# team8_solar_tester.net
KiCad netlist of a schematic drawn in EAGLE
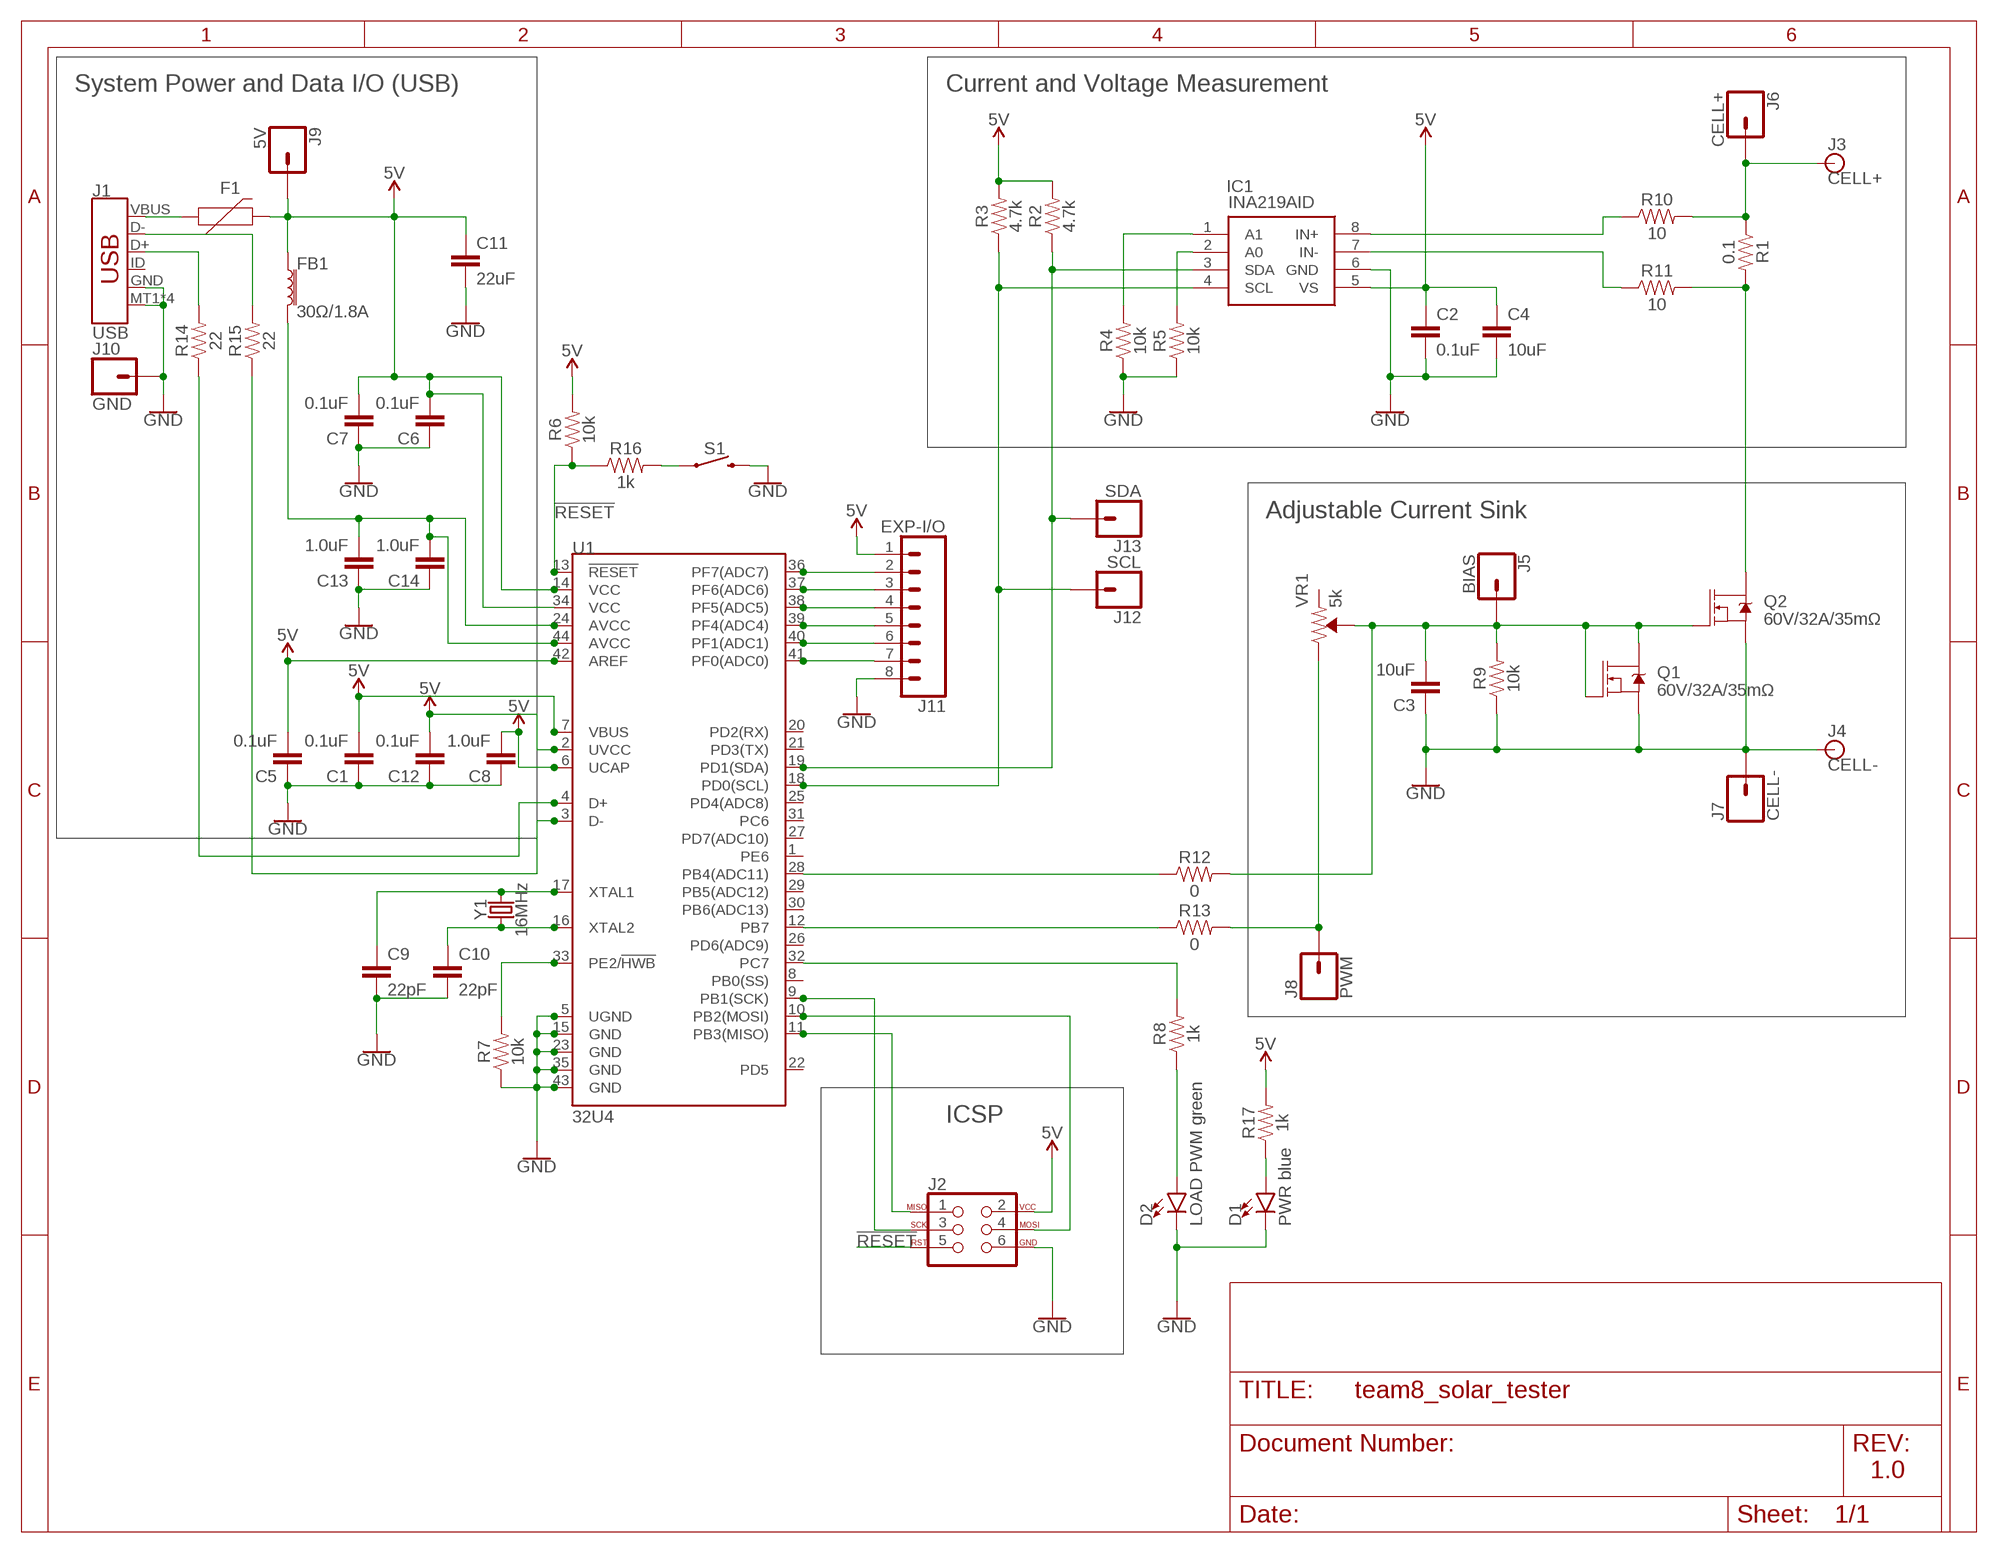
[diagram p0: schematic, sheet 1]

(export (version "E")
  (design (tool "Eeschema 10.0.6"))
  (components
    (comp (ref "C1")
      (value "0.1uF")
      (footprint "eagle-import:0603")
      (libsource (lib "eagle-import") (part "0.1UF-0603-25V-5%"))
    )
    (comp (ref "C2")
      (value "0.1uF")
      (footprint "eagle-import:0603")
      (libsource (lib "eagle-import") (part "0.1UF-0603-25V-5%"))
    )
    (comp (ref "C3")
      (value "10uF")
      (footprint "eagle-import:0805")
      (libsource (lib "eagle-import") (part "10UF-0805-10V-10%"))
    )
    (comp (ref "C4")
      (value "10uF")
      (footprint "eagle-import:0805")
      (libsource (lib "eagle-import") (part "10UF-0805-10V-10%"))
    )
    (comp (ref "C5")
      (value "0.1uF")
      (footprint "eagle-import:0603")
      (libsource (lib "eagle-import") (part "0.1UF-0603-25V-5%"))
    )
    (comp (ref "C6")
      (value "0.1uF")
      (footprint "eagle-import:0603")
      (libsource (lib "eagle-import") (part "0.1UF-0603-25V-5%"))
    )
    (comp (ref "C7")
      (value "0.1uF")
      (footprint "eagle-import:0603")
      (libsource (lib "eagle-import") (part "0.1UF-0603-25V-5%"))
    )
    (comp (ref "C8")
      (value "1.0uF")
      (footprint "eagle-import:0603")
      (libsource (lib "eagle-import") (part "1.0UF-0603-16V-10%"))
    )
    (comp (ref "C9")
      (value "22pF")
      (footprint "eagle-import:0603")
      (libsource (lib "eagle-import") (part "22PF-0603-50V-5%"))
    )
    (comp (ref "C10")
      (value "22pF")
      (footprint "eagle-import:0603")
      (libsource (lib "eagle-import") (part "22PF-0603-50V-5%"))
    )
    (comp (ref "C11")
      (value "22uF")
      (footprint "eagle-import:0805")
      (libsource (lib "eagle-import") (part "22UF-0805-6.3V-20%"))
    )
    (comp (ref "C12")
      (value "0.1uF")
      (footprint "eagle-import:0603")
      (libsource (lib "eagle-import") (part "0.1UF-0603-25V-5%"))
    )
    (comp (ref "C13")
      (value "1.0uF")
      (footprint "eagle-import:0603")
      (libsource (lib "eagle-import") (part "1.0UF-0603-16V-10%"))
    )
    (comp (ref "C14")
      (value "1.0uF")
      (footprint "eagle-import:0603")
      (libsource (lib "eagle-import") (part "1.0UF-0603-16V-10%"))
    )
    (comp (ref "D1")
      (value "PWR blue")
      (footprint "eagle-import:LED-0603")
      (libsource (lib "eagle-import") (part "LED-BLUE0603"))
    )
    (comp (ref "D2")
      (value "LOAD PWM green")
      (footprint "eagle-import:LED-0603")
      (libsource (lib "eagle-import") (part "LED-GREEN0603"))
    )
    (comp (ref "F1")
      (value "PPTC_6V500MA")
      (footprint "eagle-import:0805")
      (libsource (lib "eagle-import") (part "PPTC_6V500MA"))
    )
    (comp (ref "FB1")
      (value "30Ω/1.8A")
      (footprint "eagle-import:0603")
      (libsource (lib "eagle-import") (part "FERRITE_BEAD-0603"))
    )
    (comp (ref "IC1")
      (value "INA219AID")
      (footprint "eagle-import:SOIC127P600X175-8N")
      (fields (field (name "MOUSER_PART_NUMBER") "595-INA219AID"))
      (libsource (lib "eagle-import") (part "INA219AID"))
    )
    (comp (ref "J1")
      (value "USB")
      (footprint "eagle-import:USB-MICROB")
      (libsource (lib "eagle-import") (part "USB_MICRO-B_SMT"))
    )
    (comp (ref "J2")
      (value "AVR_SPI_PROG_3X2PTH")
      (footprint "eagle-import:2X3")
      (libsource (lib "eagle-import") (part "AVR_SPI_PROG_3X2PTH"))
    )
    (comp (ref "J3")
      (value "CELL+")
      (footprint "eagle-import:BANANA_CONN")
      (libsource (lib "eagle-import") (part "BANANA_CONN"))
    )
    (comp (ref "J4")
      (value "CELL-")
      (footprint "eagle-import:BANANA_CONN")
      (libsource (lib "eagle-import") (part "BANANA_CONN"))
    )
    (comp (ref "J5")
      (value "BIAS")
      (footprint "eagle-import:1X01")
      (libsource (lib "eagle-import") (part "CONN_01"))
    )
    (comp (ref "J6")
      (value "CELL+")
      (footprint "eagle-import:1X01")
      (libsource (lib "eagle-import") (part "CONN_01"))
    )
    (comp (ref "J7")
      (value "CELL-")
      (footprint "eagle-import:1X01")
      (libsource (lib "eagle-import") (part "CONN_01"))
    )
    (comp (ref "J8")
      (value "PWM")
      (footprint "eagle-import:1X01")
      (libsource (lib "eagle-import") (part "CONN_01"))
    )
    (comp (ref "J9")
      (value "5V")
      (footprint "eagle-import:1X01")
      (libsource (lib "eagle-import") (part "CONN_01"))
    )
    (comp (ref "J10")
      (value "GND")
      (footprint "eagle-import:1X01")
      (libsource (lib "eagle-import") (part "CONN_01"))
    )
    (comp (ref "J11")
      (value "EXP-I/O")
      (footprint "eagle-import:1X08_LONGPADS")
      (libsource (lib "eagle-import") (part "CONN_08LONGPADS"))
    )
    (comp (ref "J12")
      (value "SCL")
      (footprint "eagle-import:1X01")
      (libsource (lib "eagle-import") (part "CONN_01"))
    )
    (comp (ref "J13")
      (value "SDA")
      (footprint "eagle-import:1X01")
      (libsource (lib "eagle-import") (part "CONN_01"))
    )
    (comp (ref "Q1")
      (value "60V/32A/35mΩ")
      (footprint "eagle-import:TO220V")
      (libsource (lib "eagle-import") (part "MOSFET-NCH-FQP30N06L"))
    )
    (comp (ref "Q2")
      (value "60V/32A/35mΩ")
      (footprint "eagle-import:TO220V")
      (libsource (lib "eagle-import") (part "MOSFET-NCH-FQP30N06L"))
    )
    (comp (ref "R1")
      (value "0.1")
      (footprint "eagle-import:1210")
      (libsource (lib "eagle-import") (part "0.1OHM-1210-1/2W-1%"))
    )
    (comp (ref "R2")
      (value "4.7k")
      (footprint "eagle-import:0603")
      (libsource (lib "eagle-import") (part "4.7KOHM-0603-1/10W-1%"))
    )
    (comp (ref "R3")
      (value "4.7k")
      (footprint "eagle-import:0603")
      (libsource (lib "eagle-import") (part "4.7KOHM-0603-1/10W-1%"))
    )
    (comp (ref "R4")
      (value "10k")
      (footprint "eagle-import:0603")
      (libsource (lib "eagle-import") (part "10KOHM-0603-1/10W-1%"))
    )
    (comp (ref "R5")
      (value "10k")
      (footprint "eagle-import:0603")
      (libsource (lib "eagle-import") (part "10KOHM-0603-1/10W-1%"))
    )
    (comp (ref "R6")
      (value "10k")
      (footprint "eagle-import:0603")
      (libsource (lib "eagle-import") (part "10KOHM-0603-1/10W-1%"))
    )
    (comp (ref "R7")
      (value "10k")
      (footprint "eagle-import:0603")
      (libsource (lib "eagle-import") (part "10KOHM-0603-1/10W-1%"))
    )
    (comp (ref "R8")
      (value "1k")
      (footprint "eagle-import:0603")
      (libsource (lib "eagle-import") (part "1KOHM-0603-1/10W-1%"))
    )
    (comp (ref "R9")
      (value "10k")
      (footprint "eagle-import:0603")
      (libsource (lib "eagle-import") (part "10KOHM-0603-1/10W-1%"))
    )
    (comp (ref "R10")
      (value "10")
      (footprint "eagle-import:0603")
      (libsource (lib "eagle-import") (part "10OHM-0603-1/10W-1%"))
    )
    (comp (ref "R11")
      (value "10")
      (footprint "eagle-import:0603")
      (libsource (lib "eagle-import") (part "10OHM-0603-1/10W-1%"))
    )
    (comp (ref "R12")
      (value "0")
      (footprint "eagle-import:0603")
      (libsource (lib "eagle-import") (part "0OHM-0603-1/10W-5%"))
    )
    (comp (ref "R13")
      (value "0")
      (footprint "eagle-import:0603")
      (libsource (lib "eagle-import") (part "0OHM-0603-1/10W-5%"))
    )
    (comp (ref "R14")
      (value "22")
      (footprint "eagle-import:0603")
      (libsource (lib "eagle-import") (part "22OHM-0603-1/10W-1%"))
    )
    (comp (ref "R15")
      (value "22")
      (footprint "eagle-import:0603")
      (libsource (lib "eagle-import") (part "22OHM-0603-1/10W-1%"))
    )
    (comp (ref "R16")
      (value "1k")
      (footprint "eagle-import:0603")
      (libsource (lib "eagle-import") (part "1KOHM-0603-1/10W-1%"))
    )
    (comp (ref "R17")
      (value "1k")
      (footprint "eagle-import:0603")
      (libsource (lib "eagle-import") (part "1KOHM-0603-1/10W-1%"))
    )
    (comp (ref "S1")
      (value "MOMENTARY-SWITCH-SPST-PTH-6.0MM")
      (footprint "eagle-import:TACTILE_SWITCH_PTH_6.0MM")
      (libsource (lib "eagle-import") (part "MOMENTARY-SWITCH-SPST-PTH-6.0MM"))
    )
    (comp (ref "U1")
      (value "32U4")
      (footprint "eagle-import:QFN-44")
      (libsource (lib "eagle-import") (part "ATMEGA32U4QFN"))
    )
    (comp (ref "VR1")
      (value "5k")
      (footprint "eagle-import:TRIMPOT-SMD-5MM")
      (libsource (lib "eagle-import") (part "TRIMPOT-SMD-5MM-CLOSED-1/4W-20%"))
    )
    (comp (ref "Y1")
      (value "16MHz")
      (footprint "eagle-import:CRYSTAL-SMD-5X3.2-4PAD")
      (libsource (lib "eagle-import") (part "CRYSTAL-16MHZSMD-5X3.2"))
    )
  )
  (nets
    (net (code "1") (name "/~{RESET}") (class "Default")
      (node (ref "J2") (pin "5") (pinfunction "5_5") (pintype "passive"))
      (node (ref "R16") (pin "1") (pinfunction "1_1") (pintype "passive"))
      (node (ref "R6") (pin "1") (pinfunction "1_1") (pintype "passive"))
      (node (ref "U1") (pin "13") (pinfunction "~{RESET}_13") (pintype "bidirectional"))
    )
    (net (code "2") (name "5V") (class "Default")
      (node (ref "C1") (pin "2") (pinfunction "2_2") (pintype "passive"))
      (node (ref "C11") (pin "1") (pinfunction "1_1") (pintype "passive"))
      (node (ref "C12") (pin "2") (pinfunction "2_2") (pintype "passive"))
      (node (ref "C2") (pin "1") (pinfunction "1_1") (pintype "passive"))
      (node (ref "C4") (pin "1") (pinfunction "1_1") (pintype "passive"))
      (node (ref "C5") (pin "2") (pinfunction "2_2") (pintype "passive"))
      (node (ref "C6") (pin "2") (pinfunction "2_2") (pintype "passive"))
      (node (ref "C7") (pin "2") (pinfunction "2_2") (pintype "passive"))
      (node (ref "C8") (pin "2") (pinfunction "2_2") (pintype "passive"))
      (node (ref "F1") (pin "2") (pinfunction "2_2") (pintype "bidirectional"))
      (node (ref "FB1") (pin "1") (pinfunction "1_1") (pintype "passive"))
      (node (ref "IC1") (pin "5") (pinfunction "VS_5") (pintype "bidirectional"))
      (node (ref "J11") (pin "1") (pinfunction "1_1") (pintype "passive"))
      (node (ref "J2") (pin "2") (pinfunction "2_2") (pintype "passive"))
      (node (ref "J9") (pin "1") (pinfunction "1_1") (pintype "passive"))
      (node (ref "R17") (pin "2") (pinfunction "2_2") (pintype "passive"))
      (node (ref "R2") (pin "2") (pinfunction "2_2") (pintype "passive"))
      (node (ref "R3") (pin "2") (pinfunction "2_2") (pintype "passive"))
      (node (ref "R6") (pin "2") (pinfunction "2_2") (pintype "passive"))
      (node (ref "U1") (pin "14") (pinfunction "VCC_14") (pintype "bidirectional"))
      (node (ref "U1") (pin "2") (pinfunction "UVCC_2") (pintype "bidirectional"))
      (node (ref "U1") (pin "34") (pinfunction "VCC_34") (pintype "bidirectional"))
      (node (ref "U1") (pin "42") (pinfunction "AREF_42") (pintype "bidirectional"))
      (node (ref "U1") (pin "6") (pinfunction "UCAP_6") (pintype "bidirectional"))
      (node (ref "U1") (pin "7") (pinfunction "VBUS_7") (pintype "bidirectional"))
    )
    (net (code "3") (name "GND") (class "Default")
      (node (ref "C1") (pin "1") (pinfunction "1_1") (pintype "passive"))
      (node (ref "C10") (pin "2") (pinfunction "2_2") (pintype "passive"))
      (node (ref "C11") (pin "2") (pinfunction "2_2") (pintype "passive"))
      (node (ref "C12") (pin "1") (pinfunction "1_1") (pintype "passive"))
      (node (ref "C13") (pin "1") (pinfunction "1_1") (pintype "passive"))
      (node (ref "C14") (pin "1") (pinfunction "1_1") (pintype "passive"))
      (node (ref "C2") (pin "2") (pinfunction "2_2") (pintype "passive"))
      (node (ref "C3") (pin "1") (pinfunction "1_1") (pintype "passive"))
      (node (ref "C4") (pin "2") (pinfunction "2_2") (pintype "passive"))
      (node (ref "C5") (pin "1") (pinfunction "1_1") (pintype "passive"))
      (node (ref "C6") (pin "1") (pinfunction "1_1") (pintype "passive"))
      (node (ref "C7") (pin "1") (pinfunction "1_1") (pintype "passive"))
      (node (ref "C8") (pin "1") (pinfunction "1_1") (pintype "passive"))
      (node (ref "C9") (pin "2") (pinfunction "2_2") (pintype "passive"))
      (node (ref "D1") (pin "C") (pinfunction "C_C") (pintype "passive"))
      (node (ref "D2") (pin "C") (pinfunction "C_C") (pintype "passive"))
      (node (ref "IC1") (pin "6") (pinfunction "GND_6") (pintype "bidirectional"))
      (node (ref "J1") (pin "GND") (pinfunction "GND_GND") (pintype "power_in"))
      (node (ref "J1") (pin "MT1") (pinfunction "SHIELD_MT1") (pintype "bidirectional"))
      (node (ref "J1") (pin "MT2") (pinfunction "SHIELD_MT2") (pintype "bidirectional"))
      (node (ref "J1") (pin "P$1") (pinfunction "SHIELD_P$1") (pintype "bidirectional"))
      (node (ref "J1") (pin "P$2") (pinfunction "SHIELD_P$2") (pintype "bidirectional"))
      (node (ref "J10") (pin "1") (pinfunction "1_1") (pintype "passive"))
      (node (ref "J11") (pin "8") (pinfunction "8_8") (pintype "passive"))
      (node (ref "J2") (pin "6") (pinfunction "6_6") (pintype "passive"))
      (node (ref "J4") (pin "P$1") (pinfunction "1_P$1") (pintype "passive"))
      (node (ref "J7") (pin "1") (pinfunction "1_1") (pintype "passive"))
      (node (ref "Q1") (pin "3") (pinfunction "S_3") (pintype "bidirectional"))
      (node (ref "Q2") (pin "3") (pinfunction "S_3") (pintype "bidirectional"))
      (node (ref "R4") (pin "1") (pinfunction "1_1") (pintype "passive"))
      (node (ref "R5") (pin "1") (pinfunction "1_1") (pintype "passive"))
      (node (ref "R7") (pin "1") (pinfunction "1_1") (pintype "passive"))
      (node (ref "R9") (pin "1") (pinfunction "1_1") (pintype "passive"))
      (node (ref "S1") (pin "3") (pinfunction "2_3") (pintype "passive"))
      (node (ref "U1") (pin "15") (pinfunction "GND_15") (pintype "bidirectional"))
      (node (ref "U1") (pin "23") (pinfunction "GND_23") (pintype "bidirectional"))
      (node (ref "U1") (pin "35") (pinfunction "GND_35") (pintype "bidirectional"))
      (node (ref "U1") (pin "43") (pinfunction "GND_43") (pintype "bidirectional"))
      (node (ref "U1") (pin "5") (pinfunction "UGND_5") (pintype "bidirectional"))
    )
    (net (code "4") (name "Net-(C13-Pad2)") (class "Default")
      (node (ref "C13") (pin "2") (pinfunction "2_2") (pintype "passive"))
      (node (ref "C14") (pin "2") (pinfunction "2_2") (pintype "passive"))
      (node (ref "FB1") (pin "2") (pinfunction "2_2") (pintype "passive"))
      (node (ref "U1") (pin "24") (pinfunction "AVCC_24") (pintype "bidirectional"))
      (node (ref "U1") (pin "44") (pinfunction "AVCC_44") (pintype "bidirectional"))
    )
    (net (code "5") (name "Net-(D1-PadA)") (class "Default")
      (node (ref "D1") (pin "A") (pinfunction "A_A") (pintype "passive"))
      (node (ref "R17") (pin "1") (pinfunction "1_1") (pintype "passive"))
    )
    (net (code "6") (name "Net-(D2-PadA)") (class "Default")
      (node (ref "D2") (pin "A") (pinfunction "A_A") (pintype "passive"))
      (node (ref "R8") (pin "1") (pinfunction "1_1") (pintype "passive"))
    )
    (net (code "7") (name "Net-(F1-Pad1)") (class "Default")
      (node (ref "F1") (pin "1") (pinfunction "1_1") (pintype "bidirectional"))
      (node (ref "J1") (pin "VBUS") (pinfunction "VBUS_VBUS") (pintype "power_in"))
    )
    (net (code "8") (name "Net-(IC1-A0)") (class "Default")
      (node (ref "IC1") (pin "2") (pinfunction "A0_2") (pintype "bidirectional"))
      (node (ref "R5") (pin "2") (pinfunction "2_2") (pintype "passive"))
    )
    (net (code "9") (name "Net-(IC1-A1)") (class "Default")
      (node (ref "IC1") (pin "1") (pinfunction "A1_1") (pintype "bidirectional"))
      (node (ref "R4") (pin "2") (pinfunction "2_2") (pintype "passive"))
    )
    (net (code "10") (name "Net-(IC1-IN+)") (class "Default")
      (node (ref "IC1") (pin "8") (pinfunction "IN+_8") (pintype "bidirectional"))
      (node (ref "R10") (pin "1") (pinfunction "1_1") (pintype "passive"))
    )
    (net (code "11") (name "Net-(IC1-IN-)") (class "Default")
      (node (ref "IC1") (pin "7") (pinfunction "IN-_7") (pintype "bidirectional"))
      (node (ref "R11") (pin "1") (pinfunction "1_1") (pintype "passive"))
    )
    (net (code "12") (name "Net-(IC1-SCL)") (class "Default")
      (node (ref "IC1") (pin "4") (pinfunction "SCL_4") (pintype "bidirectional"))
      (node (ref "J12") (pin "1") (pinfunction "1_1") (pintype "passive"))
      (node (ref "R3") (pin "1") (pinfunction "1_1") (pintype "passive"))
      (node (ref "U1") (pin "18") (pinfunction "PD0(SCL)_18") (pintype "bidirectional"))
    )
    (net (code "13") (name "Net-(IC1-SDA)") (class "Default")
      (node (ref "IC1") (pin "3") (pinfunction "SDA_3") (pintype "bidirectional"))
      (node (ref "J13") (pin "1") (pinfunction "1_1") (pintype "passive"))
      (node (ref "R2") (pin "1") (pinfunction "1_1") (pintype "passive"))
      (node (ref "U1") (pin "19") (pinfunction "PD1(SDA)_19") (pintype "bidirectional"))
    )
    (net (code "14") (name "Net-(J1-PadD+)") (class "Default")
      (node (ref "J1") (pin "D+") (pinfunction "D+_D+") (pintype "bidirectional"))
      (node (ref "R14") (pin "2") (pinfunction "2_2") (pintype "passive"))
    )
    (net (code "15") (name "Net-(J1-PadD-)") (class "Default")
      (node (ref "J1") (pin "D-") (pinfunction "D-_D-") (pintype "bidirectional"))
      (node (ref "R15") (pin "2") (pinfunction "2_2") (pintype "passive"))
    )
    (net (code "16") (name "Net-(J3-1)") (class "Default")
      (node (ref "J3") (pin "P$1") (pinfunction "1_P$1") (pintype "passive"))
      (node (ref "J6") (pin "1") (pinfunction "1_1") (pintype "passive"))
      (node (ref "R1") (pin "1") (pinfunction "1_1") (pintype "passive"))
      (node (ref "R10") (pin "2") (pinfunction "2_2") (pintype "passive"))
    )
    (net (code "17") (name "Net-(Q1-D)") (class "Default")
      (node (ref "C3") (pin "2") (pinfunction "2_2") (pintype "passive"))
      (node (ref "J5") (pin "1") (pinfunction "1_1") (pintype "passive"))
      (node (ref "Q1") (pin "1") (pinfunction "G_1") (pintype "bidirectional"))
      (node (ref "Q1") (pin "2") (pinfunction "D_2") (pintype "bidirectional"))
      (node (ref "Q2") (pin "1") (pinfunction "G_1") (pintype "bidirectional"))
      (node (ref "R12") (pin "2") (pinfunction "2_2") (pintype "passive"))
      (node (ref "R9") (pin "2") (pinfunction "2_2") (pintype "passive"))
      (node (ref "VR1") (pin "B") (pinfunction "WIPER_B") (pintype "passive"))
    )
    (net (code "18") (name "Net-(Q2-D)") (class "Default")
      (node (ref "Q2") (pin "2") (pinfunction "D_2") (pintype "bidirectional"))
      (node (ref "R1") (pin "2") (pinfunction "2_2") (pintype "passive"))
      (node (ref "R11") (pin "2") (pinfunction "2_2") (pintype "passive"))
    )
    (net (code "19") (name "Net-(R16-Pad2)") (class "Default")
      (node (ref "R16") (pin "2") (pinfunction "2_2") (pintype "passive"))
      (node (ref "S1") (pin "1") (pinfunction "1_1") (pintype "passive"))
    )
    (net (code "20") (name "Net-(U1-D+)") (class "Default")
      (node (ref "R14") (pin "1") (pinfunction "1_1") (pintype "passive"))
      (node (ref "U1") (pin "4") (pinfunction "D+_4") (pintype "bidirectional"))
    )
    (net (code "21") (name "Net-(U1-D-)") (class "Default")
      (node (ref "R15") (pin "1") (pinfunction "1_1") (pintype "passive"))
      (node (ref "U1") (pin "3") (pinfunction "D-_3") (pintype "bidirectional"))
    )
    (net (code "22") (name "Net-(U1-PB1(SCK))") (class "Default")
      (node (ref "J2") (pin "3") (pinfunction "3_3") (pintype "passive"))
      (node (ref "U1") (pin "9") (pinfunction "PB1(SCK)_9") (pintype "bidirectional"))
    )
    (net (code "23") (name "Net-(U1-PB2(MOSI))") (class "Default")
      (node (ref "J2") (pin "4") (pinfunction "4_4") (pintype "passive"))
      (node (ref "U1") (pin "10") (pinfunction "PB2(MOSI)_10") (pintype "bidirectional"))
    )
    (net (code "24") (name "Net-(U1-PB3(MISO))") (class "Default")
      (node (ref "J2") (pin "1") (pinfunction "1_1") (pintype "passive"))
      (node (ref "U1") (pin "11") (pinfunction "PB3(MISO)_11") (pintype "bidirectional"))
    )
    (net (code "25") (name "Net-(U1-PB4(ADC11))") (class "Default")
      (node (ref "R12") (pin "1") (pinfunction "1_1") (pintype "passive"))
      (node (ref "U1") (pin "28") (pinfunction "PB4(ADC11)_28") (pintype "bidirectional"))
    )
    (net (code "26") (name "Net-(U1-PB7)") (class "Default")
      (node (ref "R13") (pin "1") (pinfunction "1_1") (pintype "passive"))
      (node (ref "U1") (pin "12") (pinfunction "PB7_12") (pintype "bidirectional"))
    )
    (net (code "27") (name "Net-(U1-PC7)") (class "Default")
      (node (ref "R8") (pin "2") (pinfunction "2_2") (pintype "passive"))
      (node (ref "U1") (pin "32") (pinfunction "PC7_32") (pintype "bidirectional"))
    )
    (net (code "28") (name "Net-(U1-PE2{slash}~{HWB})") (class "Default")
      (node (ref "R7") (pin "2") (pinfunction "2_2") (pintype "passive"))
      (node (ref "U1") (pin "33") (pinfunction "PE2/~{HWB}_33") (pintype "bidirectional"))
    )
    (net (code "29") (name "Net-(U1-PF0(ADC0))") (class "Default")
      (node (ref "J11") (pin "7") (pinfunction "7_7") (pintype "passive"))
      (node (ref "U1") (pin "41") (pinfunction "PF0(ADC0)_41") (pintype "bidirectional"))
    )
    (net (code "30") (name "Net-(U1-PF1(ADC1))") (class "Default")
      (node (ref "J11") (pin "6") (pinfunction "6_6") (pintype "passive"))
      (node (ref "U1") (pin "40") (pinfunction "PF1(ADC1)_40") (pintype "bidirectional"))
    )
    (net (code "31") (name "Net-(U1-PF4(ADC4))") (class "Default")
      (node (ref "J11") (pin "5") (pinfunction "5_5") (pintype "passive"))
      (node (ref "U1") (pin "39") (pinfunction "PF4(ADC4)_39") (pintype "bidirectional"))
    )
    (net (code "32") (name "Net-(U1-PF5(ADC5))") (class "Default")
      (node (ref "J11") (pin "4") (pinfunction "4_4") (pintype "passive"))
      (node (ref "U1") (pin "38") (pinfunction "PF5(ADC5)_38") (pintype "bidirectional"))
    )
    (net (code "33") (name "Net-(U1-PF6(ADC6))") (class "Default")
      (node (ref "J11") (pin "3") (pinfunction "3_3") (pintype "passive"))
      (node (ref "U1") (pin "37") (pinfunction "PF6(ADC6)_37") (pintype "bidirectional"))
    )
    (net (code "34") (name "Net-(U1-PF7(ADC7))") (class "Default")
      (node (ref "J11") (pin "2") (pinfunction "2_2") (pintype "passive"))
      (node (ref "U1") (pin "36") (pinfunction "PF7(ADC7)_36") (pintype "bidirectional"))
    )
    (net (code "35") (name "Net-(U1-XTAL1)") (class "Default")
      (node (ref "C9") (pin "1") (pinfunction "1_1") (pintype "passive"))
      (node (ref "U1") (pin "17") (pinfunction "XTAL1_17") (pintype "bidirectional"))
      (node (ref "Y1") (pin "3") (pinfunction "2_3") (pintype "passive"))
    )
    (net (code "36") (name "Net-(U1-XTAL2)") (class "Default")
      (node (ref "C10") (pin "1") (pinfunction "1_1") (pintype "passive"))
      (node (ref "U1") (pin "16") (pinfunction "XTAL2_16") (pintype "bidirectional"))
      (node (ref "Y1") (pin "1") (pinfunction "1_1") (pintype "passive"))
    )
    (net (code "37") (name "Net-(VR1-CW)") (class "Default")
      (node (ref "J8") (pin "1") (pinfunction "1_1") (pintype "passive"))
      (node (ref "R13") (pin "2") (pinfunction "2_2") (pintype "passive"))
      (node (ref "VR1") (pin "C") (pinfunction "CW_C") (pintype "passive"))
    )
    (net (code "38") (name "unconnected-(J1-PadID)") (class "Default")
      (node (ref "J1") (pin "ID") (pinfunction "ID_ID") (pintype "bidirectional"))
    )
    (net (code "39") (name "unconnected-(U1-PB0(SS)-Pad8)") (class "Default")
      (node (ref "U1") (pin "8") (pinfunction "PB0(SS)_8") (pintype "bidirectional"))
    )
    (net (code "40") (name "unconnected-(U1-PB5(ADC12)-Pad29)") (class "Default")
      (node (ref "U1") (pin "29") (pinfunction "PB5(ADC12)_29") (pintype "bidirectional"))
    )
    (net (code "41") (name "unconnected-(U1-PB6(ADC13)-Pad30)") (class "Default")
      (node (ref "U1") (pin "30") (pinfunction "PB6(ADC13)_30") (pintype "bidirectional"))
    )
    (net (code "42") (name "unconnected-(U1-PC6-Pad31)") (class "Default")
      (node (ref "U1") (pin "31") (pinfunction "PC6_31") (pintype "bidirectional"))
    )
    (net (code "43") (name "unconnected-(U1-PD2(RX)-Pad20)") (class "Default")
      (node (ref "U1") (pin "20") (pinfunction "PD2(RX)_20") (pintype "bidirectional"))
    )
    (net (code "44") (name "unconnected-(U1-PD3(TX)-Pad21)") (class "Default")
      (node (ref "U1") (pin "21") (pinfunction "PD3(TX)_21") (pintype "bidirectional"))
    )
    (net (code "45") (name "unconnected-(U1-PD4(ADC8)-Pad25)") (class "Default")
      (node (ref "U1") (pin "25") (pinfunction "PD4(ADC8)_25") (pintype "bidirectional"))
    )
    (net (code "46") (name "unconnected-(U1-PD5-Pad22)") (class "Default")
      (node (ref "U1") (pin "22") (pinfunction "PD5_22") (pintype "bidirectional"))
    )
    (net (code "47") (name "unconnected-(U1-PD6(ADC9)-Pad26)") (class "Default")
      (node (ref "U1") (pin "26") (pinfunction "PD6(ADC9)_26") (pintype "bidirectional"))
    )
    (net (code "48") (name "unconnected-(U1-PD7(ADC10)-Pad27)") (class "Default")
      (node (ref "U1") (pin "27") (pinfunction "PD7(ADC10)_27") (pintype "bidirectional"))
    )
    (net (code "49") (name "unconnected-(U1-PE6-Pad1)") (class "Default")
      (node (ref "U1") (pin "1") (pinfunction "PE6_1") (pintype "bidirectional"))
    )
    (net (code "50") (name "unconnected-(VR1-CCW-PadA)") (class "Default")
      (node (ref "VR1") (pin "A") (pinfunction "CCW_A") (pintype "passive"))
    )
  )
)
